# USB.net
KiCad netlist of a schematic drawn in Altium Designer
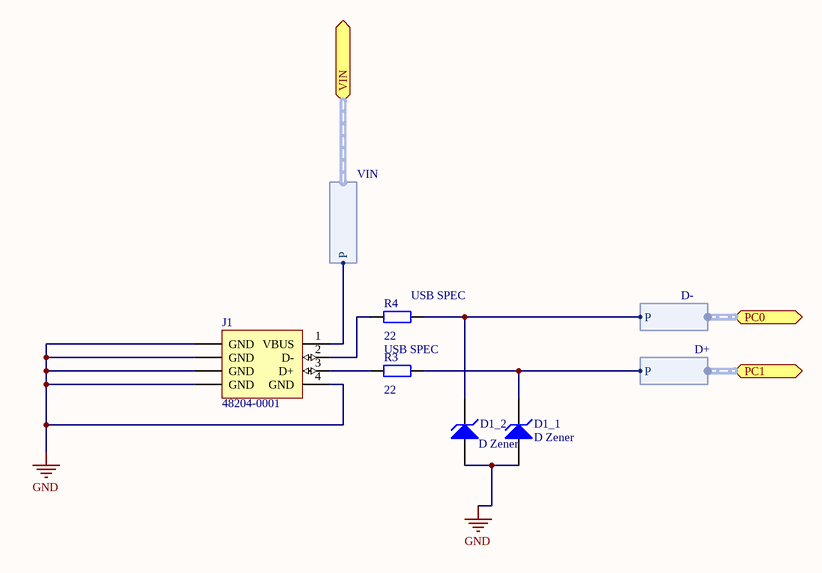
[diagram p0: USB.SchDoc]

(export (version "E")
  (design (tool "Eeschema 10.0.6"))
  (components
    (comp (ref "D1_1")
      (value "D Zener")
      (footprint "DIODE-0.7")
      (description "Zener Diode")
      (fields (field (name "PUBLISHER") "Altium Limited"))
      (libsource (lib "Miscellaneous Devices") (part "D Zener"))
    )
    (comp (ref "D1_2")
      (value "D Zener")
      (footprint "DIODE-0.7")
      (description "Zener Diode")
      (fields (field (name "PUBLISHER") "Altium Limited"))
      (libsource (lib "Miscellaneous Devices") (part "D Zener"))
    )
    (comp (ref "J1")
      (value "48204-0001")
      (footprint "MOLX-48204-0001_V")
      (description "USB Shielded I/O Receptacle, Type A")
      (fields (field (name "MANUFACTURER") "Molex"))
      (libsource (lib "Altium Content Vault") (part "CMP-0411-00001-1"))
    )
    (comp (ref "R3")
      (value "USB SPEC")
      (footprint "AXIAL-0.4")
      (description "Resistor")
      (fields (field (name "ALTIUM_VALUE") "22") (field (name "PUBLISHER") "Altium Limited"))
      (libsource (lib "Miscellaneous Devices") (part "Res2"))
    )
    (comp (ref "R4")
      (value "USB SPEC")
      (footprint "AXIAL-0.4")
      (description "Resistor")
      (fields (field (name "ALTIUM_VALUE") "22") (field (name "PUBLISHER") "Altium Limited"))
      (libsource (lib "Miscellaneous Devices") (part "Res2"))
    )
  )
  (nets
    (net (code "7") (name "GND") (class "Default")
      (node (ref "D1_1") (pin "1") (pinfunction "A_1") (pintype "passive"))
      (node (ref "D1_2") (pin "1") (pinfunction "A_1") (pintype "passive"))
      (node (ref "J1") (pin "4") (pinfunction "GND_4") (pintype "power_in"))
      (node (ref "J1") (pin "5") (pinfunction "GND_5") (pintype "power_in"))
      (node (ref "J1") (pin "6") (pinfunction "GND_6") (pintype "power_in"))
      (node (ref "J1") (pin "7") (pinfunction "GND_7") (pintype "power_in"))
      (node (ref "J1") (pin "8") (pinfunction "GND_8") (pintype "power_in"))
    )
    (net (code "8") (name "Net-(D1_1-K)") (class "Default")
      (node (ref "D1_1") (pin "2") (pinfunction "K_2") (pintype "passive"))
      (node (ref "R3") (pin "2") (pinfunction "2_2") (pintype "passive"))
    )
    (net (code "9") (name "Net-(D1_2-K)") (class "Default")
      (node (ref "D1_2") (pin "2") (pinfunction "K_2") (pintype "passive"))
      (node (ref "R4") (pin "2") (pinfunction "2_2") (pintype "passive"))
    )
    (net (code "10") (name "Net-(J1-D+)") (class "Default")
      (node (ref "J1") (pin "3") (pinfunction "D+_3") (pintype "bidirectional"))
      (node (ref "R3") (pin "1") (pinfunction "1_1") (pintype "passive"))
    )
    (net (code "11") (name "Net-(J1-D-)") (class "Default")
      (node (ref "J1") (pin "2") (pinfunction "D-_2") (pintype "bidirectional"))
      (node (ref "R4") (pin "1") (pinfunction "1_1") (pintype "passive"))
    )
    (net (code "12") (name "unconnected-(J1-VBUS-Pad1)") (class "Default")
      (node (ref "J1") (pin "1") (pinfunction "VBUS_1") (pintype "power_in"))
    )
  )
)
